# LifeBoardV1_2.net
KiCad netlist of a schematic drawn in EAGLE
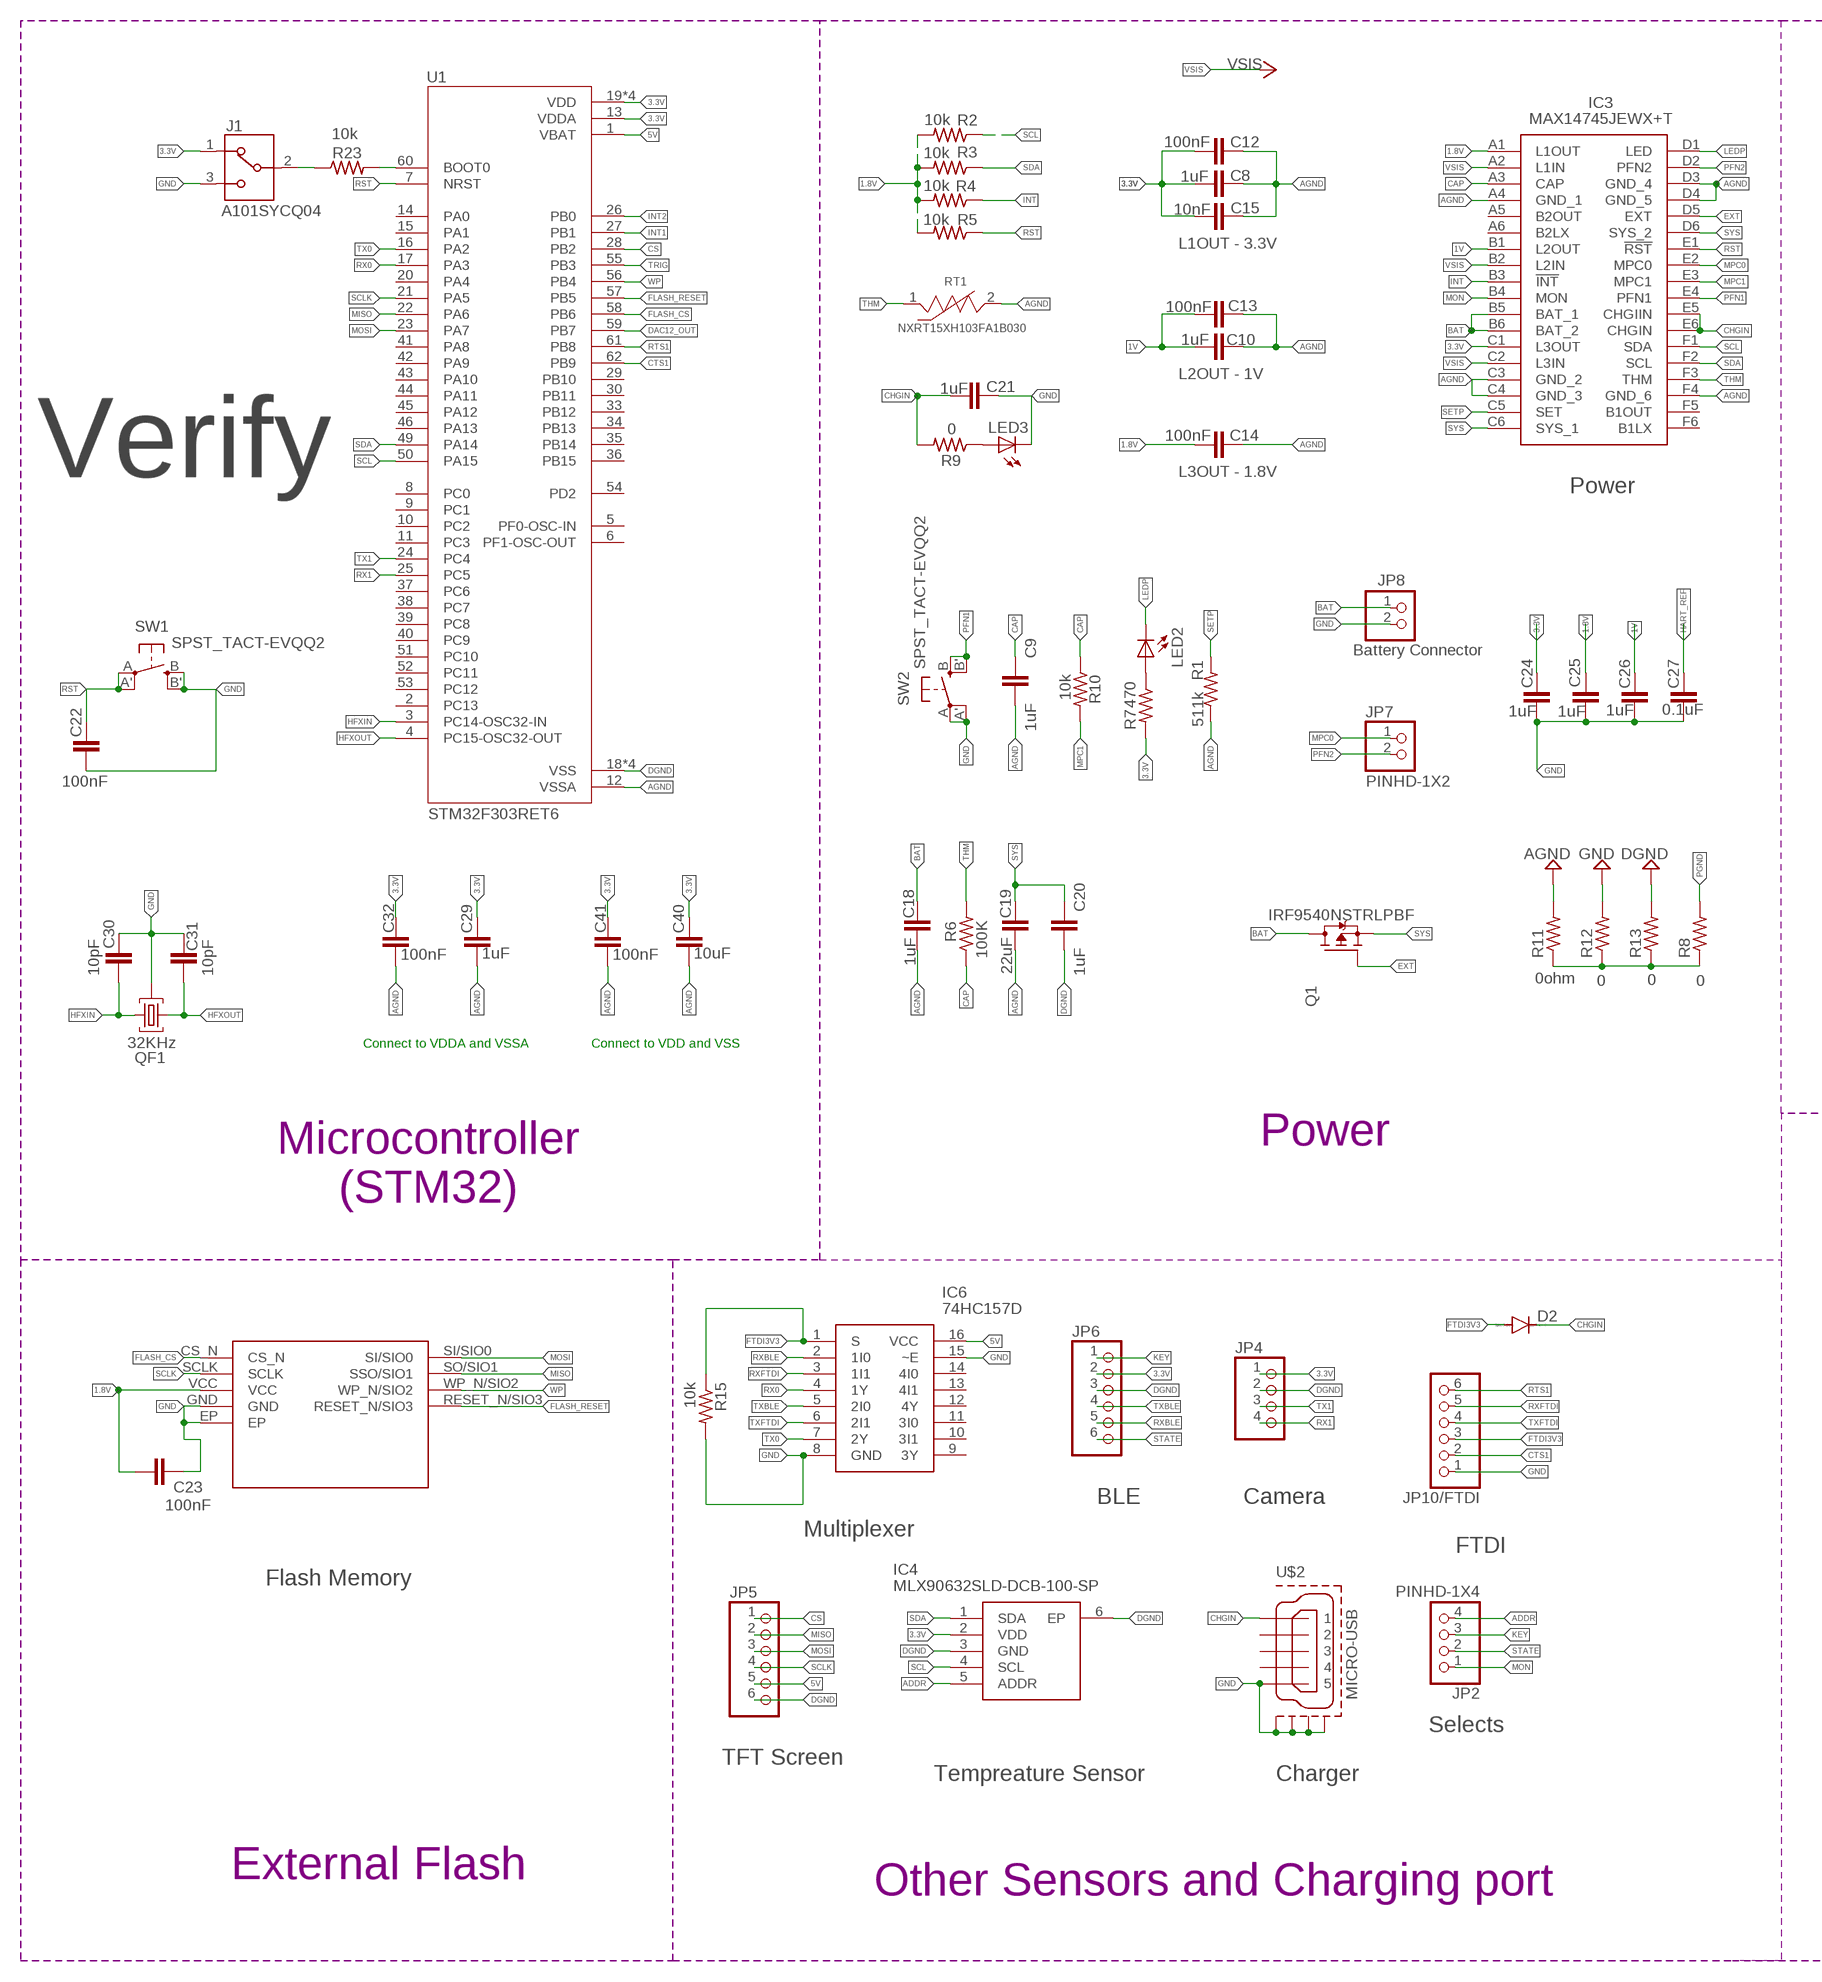
[diagram p0: schematic, sheet 1, part 1 of 2]
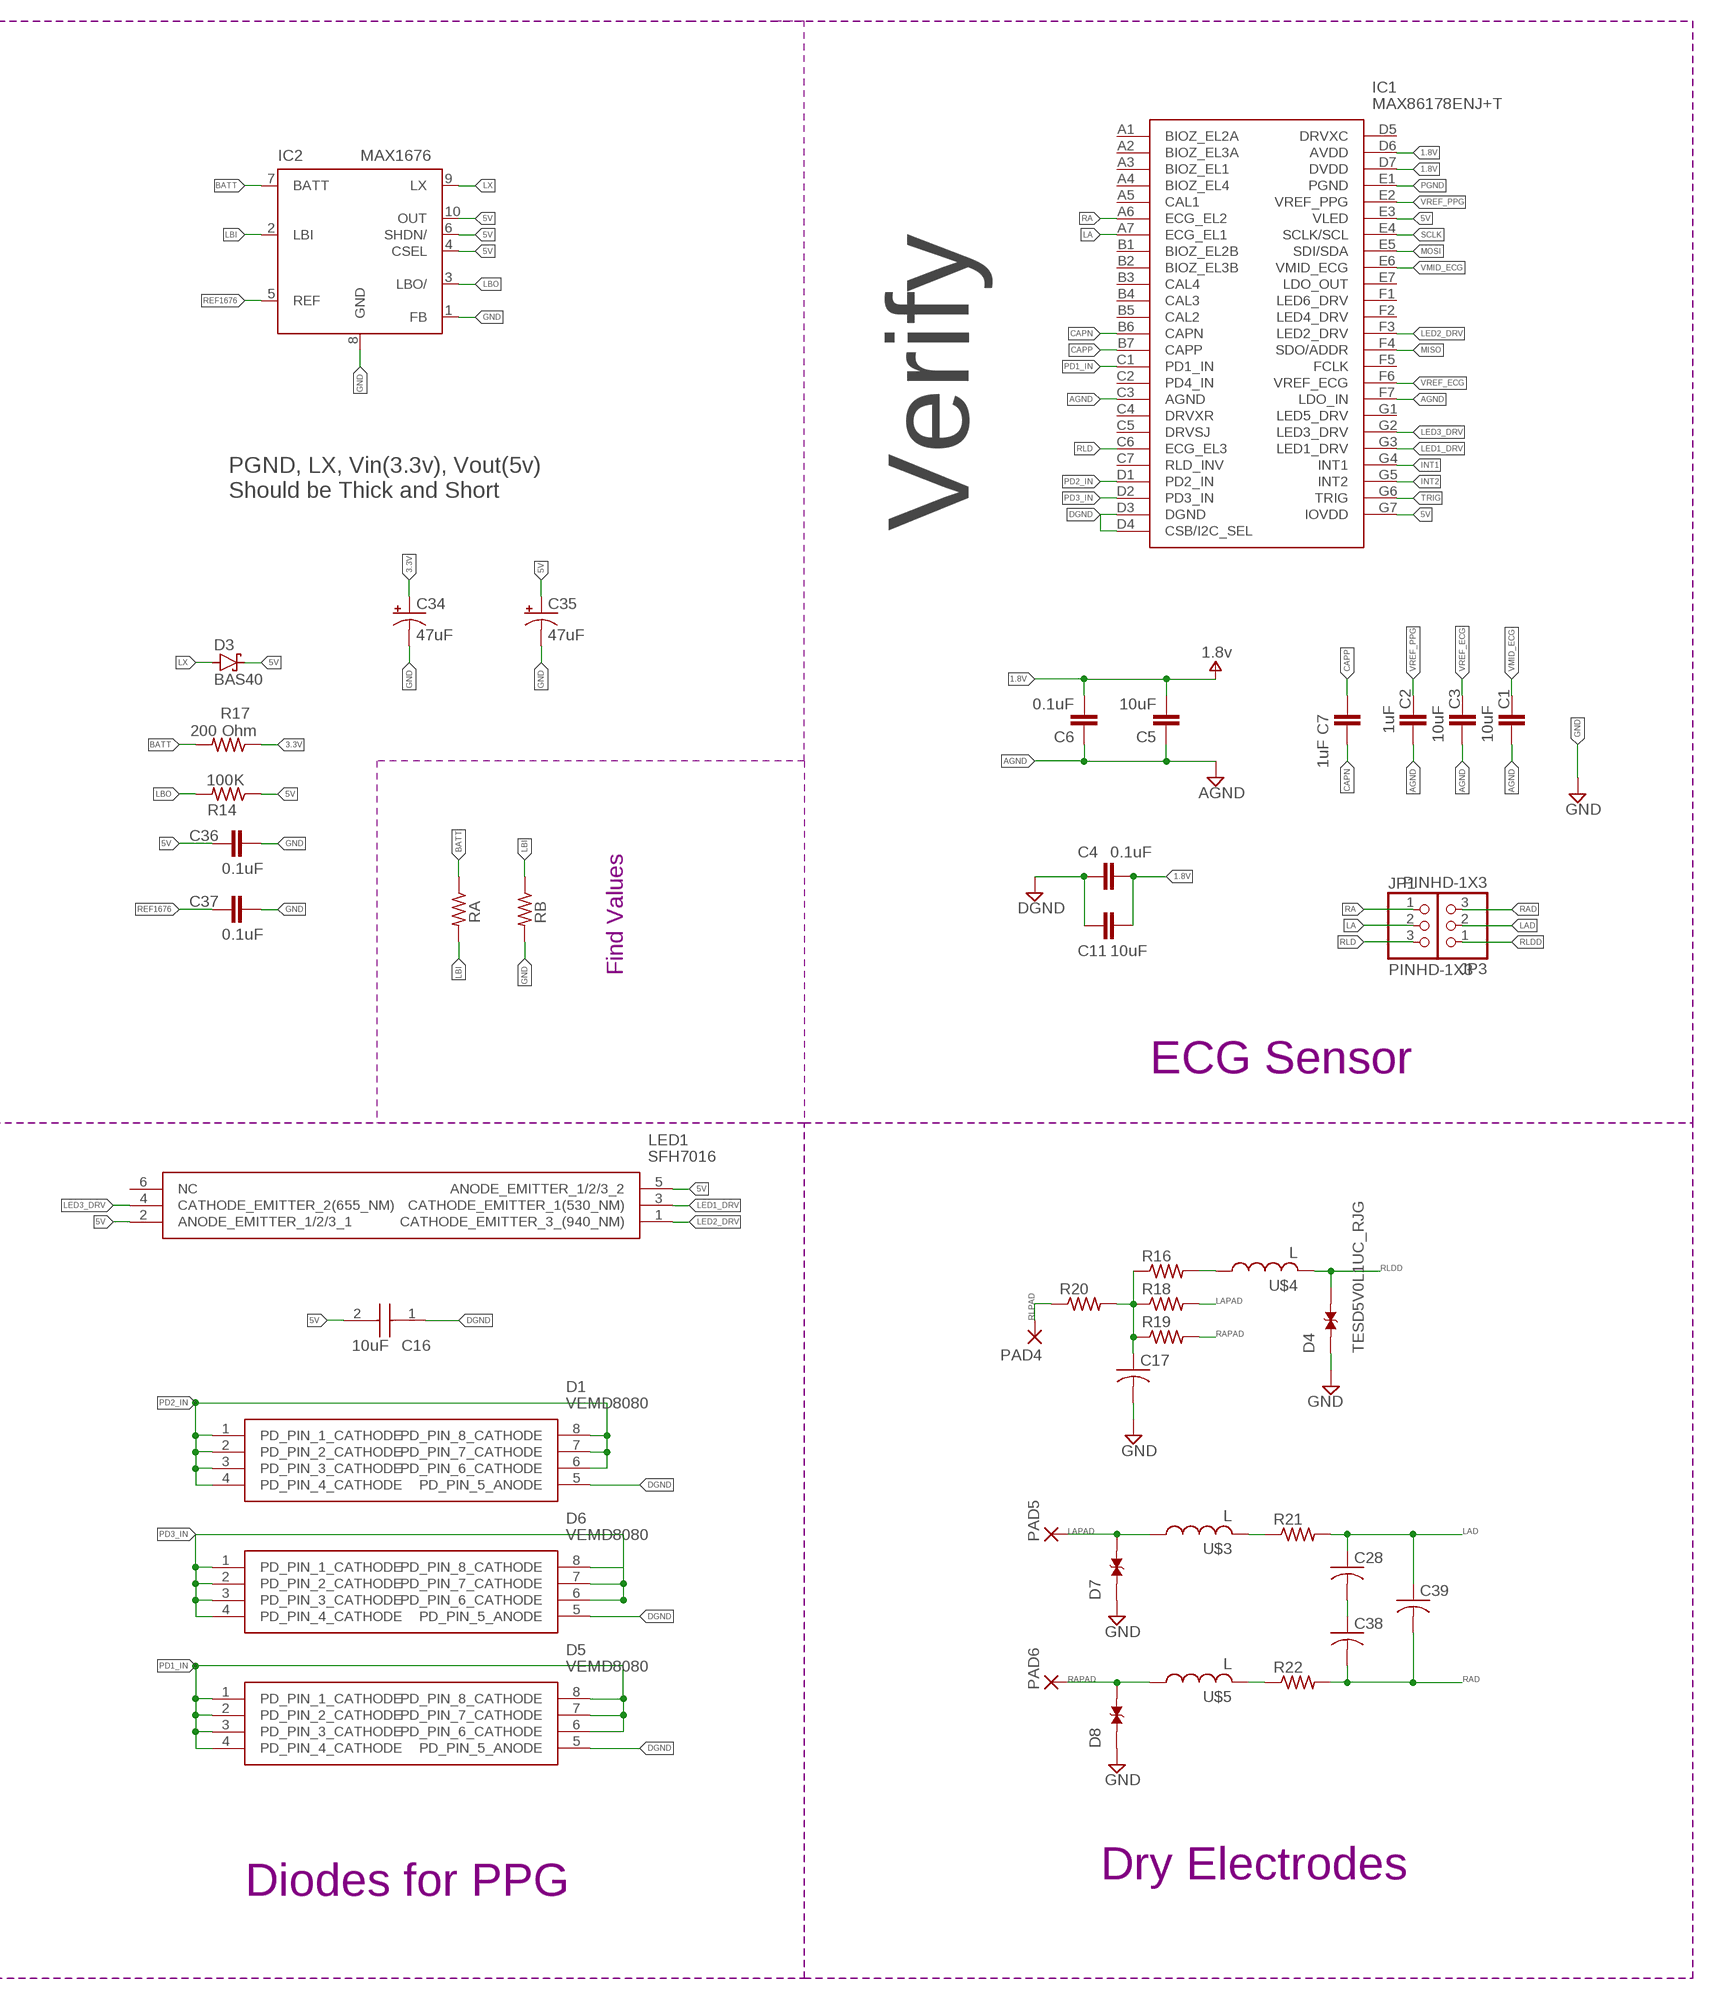
[diagram p1: schematic, sheet 1, part 2 of 2]

(export (version "E")
  (design (tool "Eeschema 10.0.6"))
  (components
    (comp (ref "C1")
      (value "10uF")
      (footprint "eagle-import:C0805")
      (libsource (lib "eagle-import") (part "C-EUC0805"))
    )
    (comp (ref "C2")
      (value "1uF")
      (footprint "eagle-import:C0805")
      (libsource (lib "eagle-import") (part "C-EUC0805"))
    )
    (comp (ref "C3")
      (value "10uF")
      (footprint "eagle-import:C0805")
      (libsource (lib "eagle-import") (part "C-EUC0805"))
    )
    (comp (ref "C4")
      (value "0.1uF")
      (footprint "eagle-import:C0805")
      (libsource (lib "eagle-import") (part "C-EUC0805"))
    )
    (comp (ref "C5")
      (value "10uF")
      (footprint "eagle-import:C0805")
      (libsource (lib "eagle-import") (part "C-EUC0805"))
    )
    (comp (ref "C6")
      (value "0.1uF")
      (footprint "eagle-import:C0805")
      (libsource (lib "eagle-import") (part "C-EUC0805"))
    )
    (comp (ref "C7")
      (value "1uF")
      (footprint "eagle-import:C0805")
      (libsource (lib "eagle-import") (part "C-EUC0805"))
    )
    (comp (ref "C8")
      (value "1uF")
      (footprint "eagle-import:C0805")
      (libsource (lib "eagle-import") (part "C-EUC0805"))
    )
    (comp (ref "C9")
      (value "1uF")
      (footprint "eagle-import:C0805")
      (libsource (lib "eagle-import") (part "C-EUC0805"))
    )
    (comp (ref "C10")
      (value "1uF")
      (footprint "eagle-import:C0805")
      (libsource (lib "eagle-import") (part "C-EUC0805"))
    )
    (comp (ref "C11")
      (value "10uF")
      (footprint "eagle-import:C0805")
      (libsource (lib "eagle-import") (part "C-EUC0805"))
    )
    (comp (ref "C12")
      (value "100nF")
      (footprint "eagle-import:C0805")
      (libsource (lib "eagle-import") (part "C-EUC0805"))
    )
    (comp (ref "C13")
      (value "100nF")
      (footprint "eagle-import:C0805")
      (libsource (lib "eagle-import") (part "C-EUC0805"))
    )
    (comp (ref "C14")
      (value "100nF")
      (footprint "eagle-import:C0805")
      (libsource (lib "eagle-import") (part "C-EUC0805"))
    )
    (comp (ref "C15")
      (value "10nF")
      (footprint "eagle-import:C0805")
      (libsource (lib "eagle-import") (part "C-EUC0805"))
    )
    (comp (ref "C16")
      (value "10uF")
      (footprint "eagle-import:CAPC1608X90N")
      (fields
        (field (name "ARROW_PART_NUMBER") "GRM188R61E106MA73L")
        (field (name "MOUSER_PART_NUMBER") "81-GRM188R61E106MA3L")
      )
      (libsource (lib "eagle-import") (part "GRM188R61E106MA73L"))
    )
    (comp (ref "C17")
      (value "C-US025-024X044")
      (footprint "eagle-import:C025-024X044")
      (libsource (lib "eagle-import") (part "C-US025-024X044"))
    )
    (comp (ref "C18")
      (value "1uF")
      (footprint "eagle-import:C0805")
      (libsource (lib "eagle-import") (part "C-EUC0805"))
    )
    (comp (ref "C19")
      (value "22uF")
      (footprint "eagle-import:C0805")
      (libsource (lib "eagle-import") (part "C-EUC0805"))
    )
    (comp (ref "C20")
      (value "1uF")
      (footprint "eagle-import:C0805")
      (libsource (lib "eagle-import") (part "C-EUC0805"))
    )
    (comp (ref "C21")
      (value "1uF")
      (footprint "eagle-import:C0805")
      (libsource (lib "eagle-import") (part "C-EUC0805"))
    )
    (comp (ref "C22")
      (value "100nF")
      (footprint "eagle-import:C0805")
      (libsource (lib "eagle-import") (part "C-EUC0805"))
    )
    (comp (ref "C23")
      (value "100nF")
      (footprint "eagle-import:C0805")
      (libsource (lib "eagle-import") (part "C-EUC0805"))
    )
    (comp (ref "C24")
      (value "1uF")
      (footprint "eagle-import:C0805")
      (libsource (lib "eagle-import") (part "C-EUC0805"))
    )
    (comp (ref "C25")
      (value "1uF")
      (footprint "eagle-import:C0805")
      (libsource (lib "eagle-import") (part "C-EUC0805"))
    )
    (comp (ref "C26")
      (value "1uF")
      (footprint "eagle-import:C0805")
      (libsource (lib "eagle-import") (part "C-EUC0805"))
    )
    (comp (ref "C27")
      (value "0.1uF")
      (footprint "eagle-import:C0805")
      (libsource (lib "eagle-import") (part "C-EUC0805"))
    )
    (comp (ref "C28")
      (value "C-US025-024X044")
      (footprint "eagle-import:C025-024X044")
      (libsource (lib "eagle-import") (part "C-US025-024X044"))
    )
    (comp (ref "C29")
      (value "1uF")
      (footprint "eagle-import:C0805")
      (libsource (lib "eagle-import") (part "C-EUC0805"))
    )
    (comp (ref "C30")
      (value "10pF")
      (footprint "eagle-import:C0805")
      (libsource (lib "eagle-import") (part "C-EUC0805"))
    )
    (comp (ref "C31")
      (value "10pF")
      (footprint "eagle-import:C0805")
      (libsource (lib "eagle-import") (part "C-EUC0805"))
    )
    (comp (ref "C32")
      (value "100nF")
      (footprint "eagle-import:C0805")
      (libsource (lib "eagle-import") (part "C-EUC0805"))
    )
    (comp (ref "C34")
      (value "47uF")
      (footprint "eagle-import:153CLV-0405")
      (libsource (lib "eagle-import") (part "CPOL-US153CLV-0405"))
    )
    (comp (ref "C35")
      (value "47uF")
      (footprint "eagle-import:153CLV-0405")
      (libsource (lib "eagle-import") (part "CPOL-US153CLV-0405"))
    )
    (comp (ref "C36")
      (value "0.1uF")
      (footprint "eagle-import:C0805")
      (libsource (lib "eagle-import") (part "C-EUC0805"))
    )
    (comp (ref "C37")
      (value "0.1uF")
      (footprint "eagle-import:C0805")
      (libsource (lib "eagle-import") (part "C-EUC0805"))
    )
    (comp (ref "C38")
      (value "C-US025-024X044")
      (footprint "eagle-import:C025-024X044")
      (libsource (lib "eagle-import") (part "C-US025-024X044"))
    )
    (comp (ref "C39")
      (value "C-US025-024X044")
      (footprint "eagle-import:C025-024X044")
      (libsource (lib "eagle-import") (part "C-US025-024X044"))
    )
    (comp (ref "C40")
      (value "10uF")
      (footprint "eagle-import:C0805")
      (libsource (lib "eagle-import") (part "C-EUC0805"))
    )
    (comp (ref "C41")
      (value "100nF")
      (footprint "eagle-import:C0805")
      (libsource (lib "eagle-import") (part "C-EUC0805"))
    )
    (comp (ref "D1")
      (value "VEMD8080")
      (footprint "eagle-import:VEMD8080")
      (fields (field (name "MOUSER_PART_NUMBER") "78-VEMD8080"))
      (libsource (lib "eagle-import") (part "VEMD8080"))
    )
    (comp (ref "D2")
      (value "CGRM4001-G")
      (footprint "eagle-import:SOD-123_MINI-SMA")
      (libsource (lib "eagle-import") (part "CGRM400-G1"))
    )
    (comp (ref "D3")
      (value "BAS40")
      (footprint "eagle-import:SOT23")
      (libsource (lib "eagle-import") (part "BAS40"))
    )
    (comp (ref "D4")
      (value "TESD5V0L1UC_RJG")
      (footprint "eagle-import:DIO_TESD5V0L1UC_RJG")
      (fields (field (name "MF") "Taiwan Semiconductor Corporation") (field (name "MP") "TESD5V0L1UC RJG"))
      (libsource (lib "eagle-import") (part "TESD5V0L1UC_RJG"))
    )
    (comp (ref "D5")
      (value "VEMD8080")
      (footprint "eagle-import:VEMD8080")
      (fields (field (name "MOUSER_PART_NUMBER") "78-VEMD8080"))
      (libsource (lib "eagle-import") (part "VEMD8080"))
    )
    (comp (ref "D6")
      (value "VEMD8080")
      (footprint "eagle-import:VEMD8080")
      (fields (field (name "MOUSER_PART_NUMBER") "78-VEMD8080"))
      (libsource (lib "eagle-import") (part "VEMD8080"))
    )
    (comp (ref "D7")
      (value "TESD5V0L1UC_RJG")
      (footprint "eagle-import:DIO_TESD5V0L1UC_RJG")
      (fields (field (name "MF") "Taiwan Semiconductor Corporation") (field (name "MP") "TESD5V0L1UC RJG"))
      (libsource (lib "eagle-import") (part "TESD5V0L1UC_RJG"))
    )
    (comp (ref "D8")
      (value "TESD5V0L1UC_RJG")
      (footprint "eagle-import:DIO_TESD5V0L1UC_RJG")
      (fields (field (name "MF") "Taiwan Semiconductor Corporation") (field (name "MP") "TESD5V0L1UC RJG"))
      (libsource (lib "eagle-import") (part "TESD5V0L1UC_RJG"))
    )
    (comp (ref "IC1")
      (value "MAX86178ENJ+T")
      (footprint "eagle-import:BGA49C35P7X7_277X257X50")
      (fields (field (name "MOUSER_PART_NUMBER") "700-MAX86178ENJ+T"))
      (libsource (lib "eagle-import") (part "MAX86178ENJ+T"))
    )
    (comp (ref "IC2")
      (value "MAX1676")
      (footprint "eagle-import:UMAX10")
      (fields (field (name "MF") "Maxim Integrated"))
      (libsource (lib "eagle-import") (part "MAX1676"))
    )
    (comp (ref "IC3")
      (value "MAX14745JEWX+T")
      (footprint "eagle-import:BGA36C40P6X6_269X244X69")
      (fields (field (name "MOUSER_PART_NUMBER") "700-MAX14745JEWX+T"))
      (libsource (lib "eagle-import") (part "MAX14745JEWX+T"))
    )
    (comp (ref "IC4")
      (value "MLX90632SLD-DCB-100-SP")
      (footprint "eagle-import:MLX90632SLDDCB100SP")
      (fields (field (name "MOUSER_PART_NUMBER") "482-90632SLDDCB100SP"))
      (libsource (lib "eagle-import") (part "MLX90632SLD-DCB-100-SP"))
    )
    (comp (ref "IC6")
      (value "74HC157D")
      (footprint "eagle-import:SOIC127P600X175-16N")
      (fields (field (name "MOUSER_PART_NUMBER") "771-74HC157D"))
      (libsource (lib "eagle-import") (part "74HC157D"))
    )
    (comp (ref "J1")
      (value "A101SYCQ04")
      (footprint "eagle-import:TE_A101SYCQ04")
      (fields (field (name "COMMENT") "4-1825136-5") (field (name "MF") "TE Connectivity"))
      (libsource (lib "eagle-import") (part "A101SYCQ04"))
    )
    (comp (ref "JP1")
      (value "PINHD-1X3")
      (footprint "eagle-import:1X03")
      (libsource (lib "eagle-import") (part "PINHD-1X3"))
    )
    (comp (ref "JP2")
      (value "PINHD-1X4")
      (footprint "eagle-import:1X04")
      (libsource (lib "eagle-import") (part "PINHD-1X4"))
    )
    (comp (ref "JP3")
      (value "PINHD-1X3")
      (footprint "eagle-import:1X03")
      (libsource (lib "eagle-import") (part "PINHD-1X3"))
    )
    (comp (ref "JP4")
      (value "PINHD-1X4")
      (footprint "eagle-import:1X04")
      (libsource (lib "eagle-import") (part "pinhead_325_PINHD-1X4"))
    )
    (comp (ref "JP5")
      (value "PINHD-1X6")
      (footprint "eagle-import:1X06")
      (libsource (lib "eagle-import") (part "PINHD-1X6"))
    )
    (comp (ref "JP6")
      (value "PINHD-1X6")
      (footprint "eagle-import:1X06")
      (libsource (lib "eagle-import") (part "PINHD-1X6"))
    )
    (comp (ref "JP7")
      (value "PINHD-1X2")
      (footprint "eagle-import:1X02")
      (libsource (lib "eagle-import") (part "PINHD-1X2"))
    )
    (comp (ref "JP8")
      (value "Battery Connector")
      (footprint "eagle-import:1X02")
      (libsource (lib "eagle-import") (part "PINHD-1X2"))
    )
    (comp (ref "JP10/FTDI")
      (value "PINHD-1X6")
      (footprint "eagle-import:1X06")
      (libsource (lib "eagle-import") (part "PINHD-1X6"))
    )
    (comp (ref "LED1")
      (value "SFH7016")
      (footprint "eagle-import:SFH7016")
      (libsource (lib "eagle-import") (part "SFH7016"))
    )
    (comp (ref "LED2")
      (value "LEDCHIPLED_1206")
      (footprint "eagle-import:CHIPLED_1206")
      (libsource (lib "eagle-import") (part "LEDCHIPLED_1206"))
    )
    (comp (ref "LED3")
      (value "LEDCHIPLED_1206")
      (footprint "eagle-import:CHIPLED_1206")
      (libsource (lib "eagle-import") (part "LEDCHIPLED_1206"))
    )
    (comp (ref "PAD4")
      (value "SMD5")
      (footprint "eagle-import:SMD2,54-5,08")
      (libsource (lib "eagle-import") (part "SMD5"))
    )
    (comp (ref "PAD5")
      (value "SMD5")
      (footprint "eagle-import:SMD2,54-5,08")
      (libsource (lib "eagle-import") (part "SMD5"))
    )
    (comp (ref "PAD6")
      (value "SMD5")
      (footprint "eagle-import:SMD2,54-5,08")
      (libsource (lib "eagle-import") (part "SMD5"))
    )
    (comp (ref "Q1")
      (value "IRF9540NSTRLPBF")
      (footprint "eagle-import:DPAK254P1524X483-4_3N")
      (fields (field (name "MF") "Infineon"))
      (libsource (lib "eagle-import") (part "IRF9540NSTRLPBF"))
    )
    (comp (ref "QF1")
      (value "32KHz")
      (footprint "eagle-import:HC49U")
      (libsource (lib "eagle-import") (part "8M10AHC49T"))
    )
    (comp (ref "R1")
      (value "511k")
      (footprint "eagle-import:M1206")
      (libsource (lib "eagle-import") (part "R-US_M1206"))
    )
    (comp (ref "R2")
      (value "10k")
      (footprint "eagle-import:M1206")
      (libsource (lib "eagle-import") (part "R-US_M1206"))
    )
    (comp (ref "R3")
      (value "10k")
      (footprint "eagle-import:M1206")
      (libsource (lib "eagle-import") (part "R-US_M1206"))
    )
    (comp (ref "R4")
      (value "10k")
      (footprint "eagle-import:M1206")
      (libsource (lib "eagle-import") (part "R-US_M1206"))
    )
    (comp (ref "R5")
      (value "10k")
      (footprint "eagle-import:M1206")
      (libsource (lib "eagle-import") (part "R-US_M1206"))
    )
    (comp (ref "R6")
      (value "100K")
      (footprint "eagle-import:M1206")
      (libsource (lib "eagle-import") (part "R-US_M1206"))
    )
    (comp (ref "R7")
      (value "470")
      (footprint "eagle-import:M1206")
      (libsource (lib "eagle-import") (part "R-US_M1206"))
    )
    (comp (ref "R8")
      (value "0")
      (footprint "eagle-import:R1206")
      (libsource (lib "eagle-import") (part "R-US_R1206"))
    )
    (comp (ref "R9")
      (value "0")
      (footprint "eagle-import:R1206")
      (libsource (lib "eagle-import") (part "R-US_R1206"))
    )
    (comp (ref "R10")
      (value "10k")
      (footprint "eagle-import:M1206")
      (libsource (lib "eagle-import") (part "R-US_M1206"))
    )
    (comp (ref "R11")
      (value "0ohm")
      (footprint "eagle-import:R1206")
      (libsource (lib "eagle-import") (part "R-US_R1206"))
    )
    (comp (ref "R12")
      (value "0")
      (footprint "eagle-import:R1206")
      (libsource (lib "eagle-import") (part "R-US_R1206"))
    )
    (comp (ref "R13")
      (value "0")
      (footprint "eagle-import:R1206")
      (libsource (lib "eagle-import") (part "R-US_R1206"))
    )
    (comp (ref "R14")
      (value "100K")
      (footprint "eagle-import:R1206")
      (libsource (lib "eagle-import") (part "R-US_R1206"))
    )
    (comp (ref "R15")
      (value "10k")
      (footprint "eagle-import:M1206")
      (libsource (lib "eagle-import") (part "R-US_M1206"))
    )
    (comp (ref "R16")
      (value "R-US_0207/10")
      (footprint "eagle-import:0207_10")
      (libsource (lib "eagle-import") (part "R-US_0207/10"))
    )
    (comp (ref "R17")
      (value "200 Ohm")
      (footprint "eagle-import:R1206")
      (libsource (lib "eagle-import") (part "R-US_R1206"))
    )
    (comp (ref "R18")
      (value "R-US_0207/10")
      (footprint "eagle-import:0207_10")
      (libsource (lib "eagle-import") (part "R-US_0207/10"))
    )
    (comp (ref "R19")
      (value "R-US_0207/10")
      (footprint "eagle-import:0207_10")
      (libsource (lib "eagle-import") (part "R-US_0207/10"))
    )
    (comp (ref "R20")
      (value "R-US_0207/10")
      (footprint "eagle-import:0207_10")
      (libsource (lib "eagle-import") (part "R-US_0207/10"))
    )
    (comp (ref "R21")
      (value "R-US_0207/10")
      (footprint "eagle-import:0207_10")
      (libsource (lib "eagle-import") (part "R-US_0207/10"))
    )
    (comp (ref "R22")
      (value "R-US_0207/10")
      (footprint "eagle-import:0207_10")
      (libsource (lib "eagle-import") (part "R-US_0207/10"))
    )
    (comp (ref "R23")
      (value "10k")
      (footprint "eagle-import:M1206")
      (libsource (lib "eagle-import") (part "R-US_M1206"))
    )
    (comp (ref "RA")
      (value "R-US_R1206")
      (footprint "eagle-import:R1206")
      (libsource (lib "eagle-import") (part "R-US_R1206"))
    )
    (comp (ref "RB")
      (value "R-US_R1206")
      (footprint "eagle-import:R1206")
      (libsource (lib "eagle-import") (part "R-US_R1206"))
    )
    (comp (ref "RT1")
      (value "NXRT15XH103FA1B030")
      (footprint "eagle-import:THERM_NXRT15XH103FA1B030")
      (fields (field (name "MF") "Murata"))
      (libsource (lib "eagle-import") (part "NXRT15XH103FA1B030"))
    )
    (comp (ref "SW1")
      (value "SPST_TACT-EVQQ2")
      (footprint "eagle-import:EVQ-Q2")
      (libsource (lib "eagle-import") (part "SPST_TACT-EVQQ2"))
    )
    (comp (ref "SW2")
      (value "SPST_TACT-EVQQ2")
      (footprint "eagle-import:EVQ-Q2")
      (libsource (lib "eagle-import") (part "SPST_TACT-EVQQ2"))
    )
    (comp (ref "U$1")
      (value "FLASH")
      (footprint "eagle-import:SON127P600X800X80-9N")
      (libsource (lib "eagle-import") (part "FLASH"))
    )
    (comp (ref "U$2")
      (value "MICRO-USB")
      (footprint "eagle-import:47589-0001")
      (libsource (lib "eagle-import") (part "MICRO-USB-RECEPTACLE47589-0001"))
    )
    (comp (ref "U$3") (value "L") (footprint "eagle-import:6000") (libsource (lib "eagle-import") (part "L")))
    (comp (ref "U$4") (value "L") (footprint "eagle-import:6000") (libsource (lib "eagle-import") (part "L")))
    (comp (ref "U$5") (value "L") (footprint "eagle-import:6000") (libsource (lib "eagle-import") (part "L")))
    (comp (ref "U1")
      (value "STM32F303RET6")
      (footprint "eagle-import:QFP50P1200X1200X160-64N")
      (fields (field (name "MF") "STMicroelectronics"))
      (libsource (lib "eagle-import") (part "STM32F303RET6"))
    )
  )
  (nets
    (net (code "1") (name "/LAPAD") (class "Default")
      (node (ref "D7") (pin "2") (pinfunction "2_2") (pintype "passive"))
      (node (ref "PAD5") (pin "1") (pinfunction "P_1") (pintype "passive"))
      (node (ref "R18") (pin "2") (pinfunction "2_2") (pintype "passive"))
      (node (ref "U$3") (pin "1") (pinfunction "1_1") (pintype "passive"))
    )
    (net (code "2") (name "/RAPAD") (class "Default")
      (node (ref "D8") (pin "2") (pinfunction "2_2") (pintype "passive"))
      (node (ref "PAD6") (pin "1") (pinfunction "P_1") (pintype "passive"))
      (node (ref "R19") (pin "2") (pinfunction "2_2") (pintype "passive"))
      (node (ref "U$5") (pin "1") (pinfunction "1_1") (pintype "passive"))
    )
    (net (code "3") (name "/RLPAD") (class "Default")
      (node (ref "PAD4") (pin "1") (pinfunction "P_1") (pintype "passive"))
      (node (ref "R20") (pin "1") (pinfunction "1_1") (pintype "passive"))
    )
    (net (code "4") (name "1.8V") (class "Default")
      (node (ref "C11") (pin "2") (pinfunction "2_2") (pintype "passive"))
      (node (ref "C14") (pin "2") (pinfunction "2_2") (pintype "passive"))
      (node (ref "C23") (pin "1") (pinfunction "1_1") (pintype "passive"))
      (node (ref "C25") (pin "1") (pinfunction "1_1") (pintype "passive"))
      (node (ref "C4") (pin "2") (pinfunction "2_2") (pintype "passive"))
      (node (ref "C5") (pin "2") (pinfunction "2_2") (pintype "passive"))
      (node (ref "C6") (pin "2") (pinfunction "2_2") (pintype "passive"))
      (node (ref "IC1") (pin "D6") (pinfunction "AVDD_D6") (pintype "bidirectional"))
      (node (ref "IC1") (pin "D7") (pinfunction "DVDD_D7") (pintype "bidirectional"))
      (node (ref "IC3") (pin "A1") (pinfunction "L1OUT_A1") (pintype "bidirectional"))
      (node (ref "R2") (pin "2") (pinfunction "2_2") (pintype "passive"))
      (node (ref "R3") (pin "2") (pinfunction "2_2") (pintype "passive"))
      (node (ref "R4") (pin "2") (pinfunction "2_2") (pintype "passive"))
      (node (ref "R5") (pin "2") (pinfunction "2_2") (pintype "passive"))
      (node (ref "U$1") (pin "VCC") (pinfunction "VCC_VCC") (pintype "bidirectional"))
    )
    (net (code "5") (name "1V") (class "Default")
      (node (ref "C10") (pin "2") (pinfunction "2_2") (pintype "passive"))
      (node (ref "C13") (pin "2") (pinfunction "2_2") (pintype "passive"))
      (node (ref "C26") (pin "1") (pinfunction "1_1") (pintype "passive"))
      (node (ref "IC3") (pin "B1") (pinfunction "L2OUT_B1") (pintype "bidirectional"))
    )
    (net (code "6") (name "3.3V") (class "Default")
      (node (ref "C12") (pin "2") (pinfunction "2_2") (pintype "passive"))
      (node (ref "C15") (pin "2") (pinfunction "2_2") (pintype "passive"))
      (node (ref "C24") (pin "1") (pinfunction "1_1") (pintype "passive"))
      (node (ref "C29") (pin "1") (pinfunction "1_1") (pintype "passive"))
      (node (ref "C32") (pin "1") (pinfunction "1_1") (pintype "passive"))
      (node (ref "C34") (pin "+") (pinfunction "+_+") (pintype "passive"))
      (node (ref "C40") (pin "1") (pinfunction "1_1") (pintype "passive"))
      (node (ref "C41") (pin "1") (pinfunction "1_1") (pintype "passive"))
      (node (ref "C8") (pin "2") (pinfunction "2_2") (pintype "passive"))
      (node (ref "IC3") (pin "C1") (pinfunction "L3OUT_C1") (pintype "bidirectional"))
      (node (ref "IC4") (pin "2") (pinfunction "VDD_2") (pintype "bidirectional"))
      (node (ref "J1") (pin "1") (pinfunction "1_1") (pintype "passive"))
      (node (ref "JP4") (pin "1") (pinfunction "1_1") (pintype "passive"))
      (node (ref "JP6") (pin "2") (pinfunction "2_2") (pintype "passive"))
      (node (ref "R17") (pin "1") (pinfunction "1_1") (pintype "passive"))
      (node (ref "R7") (pin "2") (pinfunction "2_2") (pintype "passive"))
      (node (ref "U1") (pin "13") (pinfunction "VDDA_13") (pintype "power_in"))
      (node (ref "U1") (pin "19") (pinfunction "VDD_19") (pintype "power_in"))
      (node (ref "U1") (pin "32") (pinfunction "VDD_32") (pintype "power_in"))
      (node (ref "U1") (pin "48") (pinfunction "VDD_48") (pintype "power_in"))
      (node (ref "U1") (pin "64") (pinfunction "VDD_64") (pintype "power_in"))
    )
    (net (code "7") (name "5V") (class "Default")
      (node (ref "C16") (pin "2") (pinfunction "2_2") (pintype "bidirectional"))
      (node (ref "C35") (pin "+") (pinfunction "+_+") (pintype "passive"))
      (node (ref "C36") (pin "1") (pinfunction "1_1") (pintype "passive"))
      (node (ref "D3") (pin "3") (pinfunction "C_3") (pintype "passive"))
      (node (ref "IC1") (pin "E3") (pinfunction "VLED_E3") (pintype "bidirectional"))
      (node (ref "IC1") (pin "G7") (pinfunction "IOVDD_G7") (pintype "bidirectional"))
      (node (ref "IC2") (pin "10") (pinfunction "OUT_10") (pintype "output"))
      (node (ref "IC2") (pin "4") (pinfunction "CSEL_4") (pintype "input"))
      (node (ref "IC2") (pin "6") (pinfunction "SHDN/_6") (pintype "input"))
      (node (ref "IC6") (pin "16") (pinfunction "VCC_16") (pintype "bidirectional"))
      (node (ref "JP5") (pin "5") (pinfunction "5_5") (pintype "passive"))
      (node (ref "LED1") (pin "2") (pinfunction "ANODE_EMITTER_1/2/3_1_2") (pintype "bidirectional"))
      (node (ref "LED1") (pin "5") (pinfunction "ANODE_EMITTER_1/2/3_2_5") (pintype "bidirectional"))
      (node (ref "R14") (pin "1") (pinfunction "1_1") (pintype "passive"))
      (node (ref "U1") (pin "1") (pinfunction "VBAT_1") (pintype "power_in"))
    )
    (net (code "8") (name "ADDR") (class "Default")
      (node (ref "IC4") (pin "5") (pinfunction "ADDR_5") (pintype "bidirectional"))
      (node (ref "JP2") (pin "4") (pinfunction "4_4") (pintype "passive"))
    )
    (net (code "9") (name "AGND") (class "Default")
      (node (ref "C1") (pin "1") (pinfunction "1_1") (pintype "passive"))
      (node (ref "C10") (pin "1") (pinfunction "1_1") (pintype "passive"))
      (node (ref "C12") (pin "1") (pinfunction "1_1") (pintype "passive"))
      (node (ref "C13") (pin "1") (pinfunction "1_1") (pintype "passive"))
      (node (ref "C14") (pin "1") (pinfunction "1_1") (pintype "passive"))
      (node (ref "C15") (pin "1") (pinfunction "1_1") (pintype "passive"))
      (node (ref "C18") (pin "2") (pinfunction "2_2") (pintype "passive"))
      (node (ref "C19") (pin "2") (pinfunction "2_2") (pintype "passive"))
      (node (ref "C2") (pin "1") (pinfunction "1_1") (pintype "passive"))
      (node (ref "C29") (pin "2") (pinfunction "2_2") (pintype "passive"))
      (node (ref "C3") (pin "1") (pinfunction "1_1") (pintype "passive"))
      (node (ref "C32") (pin "2") (pinfunction "2_2") (pintype "passive"))
      (node (ref "C40") (pin "2") (pinfunction "2_2") (pintype "passive"))
      (node (ref "C41") (pin "2") (pinfunction "2_2") (pintype "passive"))
      (node (ref "C5") (pin "1") (pinfunction "1_1") (pintype "passive"))
      (node (ref "C6") (pin "1") (pinfunction "1_1") (pintype "passive"))
      (node (ref "C8") (pin "1") (pinfunction "1_1") (pintype "passive"))
      (node (ref "C9") (pin "2") (pinfunction "2_2") (pintype "passive"))
      (node (ref "IC1") (pin "C3") (pinfunction "AGND_C3") (pintype "bidirectional"))
      (node (ref "IC1") (pin "F7") (pinfunction "LDO_IN_F7") (pintype "bidirectional"))
      (node (ref "IC3") (pin "A4") (pinfunction "GND_1_A4") (pintype "bidirectional"))
      (node (ref "IC3") (pin "C3") (pinfunction "GND_2_C3") (pintype "bidirectional"))
      (node (ref "IC3") (pin "C4") (pinfunction "GND_3_C4") (pintype "bidirectional"))
      (node (ref "IC3") (pin "D3") (pinfunction "GND_4_D3") (pintype "bidirectional"))
      (node (ref "IC3") (pin "D4") (pinfunction "GND_5_D4") (pintype "bidirectional"))
      (node (ref "IC3") (pin "F4") (pinfunction "GND_6_F4") (pintype "bidirectional"))
      (node (ref "R1") (pin "1") (pinfunction "1_1") (pintype "passive"))
      (node (ref "R11") (pin "2") (pinfunction "2_2") (pintype "passive"))
      (node (ref "RT1") (pin "2") (pinfunction "2_2") (pintype "passive"))
      (node (ref "U1") (pin "12") (pinfunction "VSSA_12") (pintype "power_in"))
    )
    (net (code "10") (name "BAT") (class "Default")
      (node (ref "C18") (pin "1") (pinfunction "1_1") (pintype "passive"))
      (node (ref "IC3") (pin "B5") (pinfunction "BAT_1_B5") (pintype "bidirectional"))
      (node (ref "IC3") (pin "B6") (pinfunction "BAT_2_B6") (pintype "bidirectional"))
      (node (ref "JP8") (pin "1") (pinfunction "1_1") (pintype "passive"))
      (node (ref "Q1") (pin "4") (pinfunction "D_4") (pintype "passive"))
    )
    (net (code "11") (name "BATT") (class "Default")
      (node (ref "IC2") (pin "7") (pinfunction "BATT_7") (pintype "input"))
      (node (ref "R17") (pin "2") (pinfunction "2_2") (pintype "passive"))
      (node (ref "RA") (pin "1") (pinfunction "1_1") (pintype "passive"))
    )
    (net (code "12") (name "CAP") (class "Default")
      (node (ref "C9") (pin "1") (pinfunction "1_1") (pintype "passive"))
      (node (ref "IC3") (pin "A3") (pinfunction "CAP_A3") (pintype "bidirectional"))
      (node (ref "R10") (pin "1") (pinfunction "1_1") (pintype "passive"))
      (node (ref "R6") (pin "1") (pinfunction "1_1") (pintype "passive"))
    )
    (net (code "13") (name "CAPN") (class "Default")
      (node (ref "C7") (pin "2") (pinfunction "2_2") (pintype "passive"))
      (node (ref "IC1") (pin "B6") (pinfunction "CAPN_B6") (pintype "bidirectional"))
    )
    (net (code "14") (name "CAPP") (class "Default")
      (node (ref "C7") (pin "1") (pinfunction "1_1") (pintype "passive"))
      (node (ref "IC1") (pin "B7") (pinfunction "CAPP_B7") (pintype "bidirectional"))
    )
    (net (code "15") (name "CHGIN") (class "Default")
      (node (ref "C21") (pin "2") (pinfunction "2_2") (pintype "passive"))
      (node (ref "D2") (pin "C") (pinfunction "C_C") (pintype "passive"))
      (node (ref "IC3") (pin "E5") (pinfunction "CHGIIN_E5") (pintype "bidirectional"))
      (node (ref "IC3") (pin "E6") (pinfunction "CHGIN_E6") (pintype "bidirectional"))
      (node (ref "R9") (pin "2") (pinfunction "2_2") (pintype "passive"))
      (node (ref "U$2") (pin "1") (pinfunction "1_1") (pintype "input"))
    )
    (net (code "16") (name "CS") (class "Default")
      (node (ref "JP5") (pin "1") (pinfunction "1_1") (pintype "passive"))
      (node (ref "U1") (pin "28") (pinfunction "PB2_28") (pintype "bidirectional"))
    )
    (net (code "17") (name "CTS1") (class "Default")
      (node (ref "JP10/FTDI") (pin "2") (pinfunction "2_2") (pintype "passive"))
      (node (ref "U1") (pin "62") (pinfunction "PB9_62") (pintype "bidirectional"))
    )
    (net (code "18") (name "DAC12_OUT") (class "Default")
      (node (ref "U1") (pin "59") (pinfunction "PB7_59") (pintype "bidirectional"))
    )
    (net (code "19") (name "DGND") (class "Default")
      (node (ref "C11") (pin "1") (pinfunction "1_1") (pintype "passive"))
      (node (ref "C16") (pin "1") (pinfunction "1_1") (pintype "bidirectional"))
      (node (ref "C20") (pin "2") (pinfunction "2_2") (pintype "passive"))
      (node (ref "C4") (pin "1") (pinfunction "1_1") (pintype "passive"))
      (node (ref "D1") (pin "5") (pinfunction "PD_PIN_5_ANODE_5") (pintype "bidirectional"))
      (node (ref "D5") (pin "5") (pinfunction "PD_PIN_5_ANODE_5") (pintype "bidirectional"))
      (node (ref "D6") (pin "5") (pinfunction "PD_PIN_5_ANODE_5") (pintype "bidirectional"))
      (node (ref "IC1") (pin "D3") (pinfunction "DGND_D3") (pintype "bidirectional"))
      (node (ref "IC1") (pin "D4") (pinfunction "CSB/I2C_SEL_D4") (pintype "bidirectional"))
      (node (ref "IC4") (pin "3") (pinfunction "GND_3") (pintype "bidirectional"))
      (node (ref "IC4") (pin "6") (pinfunction "EP_6") (pintype "bidirectional"))
      (node (ref "JP4") (pin "2") (pinfunction "2_2") (pintype "passive"))
      (node (ref "JP5") (pin "6") (pinfunction "6_6") (pintype "passive"))
      (node (ref "JP6") (pin "3") (pinfunction "3_3") (pintype "passive"))
      (node (ref "R13") (pin "2") (pinfunction "2_2") (pintype "passive"))
      (node (ref "U1") (pin "18") (pinfunction "VSS_18") (pintype "power_in"))
      (node (ref "U1") (pin "31") (pinfunction "VSS_31") (pintype "power_in"))
      (node (ref "U1") (pin "47") (pinfunction "VSS_47") (pintype "power_in"))
      (node (ref "U1") (pin "63") (pinfunction "VSS_63") (pintype "power_in"))
    )
    (net (code "20") (name "EXT") (class "Default")
      (node (ref "IC3") (pin "D5") (pinfunction "EXT_D5") (pintype "bidirectional"))
      (node (ref "Q1") (pin "1") (pinfunction "G_1") (pintype "passive"))
    )
    (net (code "21") (name "FLASH_CS") (class "Default")
      (node (ref "U$1") (pin "CS_N") (pinfunction "CS_N_CS_N") (pintype "bidirectional"))
      (node (ref "U1") (pin "58") (pinfunction "PB6_58") (pintype "bidirectional"))
    )
    (net (code "22") (name "FLASH_RESET") (class "Default")
      (node (ref "U$1") (pin "RESET_N/SIO3") (pinfunction "RESET_N/SIO3_RESET_N/SIO3") (pintype "bidirectional"))
      (node (ref "U1") (pin "57") (pinfunction "PB5_57") (pintype "bidirectional"))
    )
    (net (code "23") (name "FTDI3V3") (class "Default")
      (node (ref "D2") (pin "A") (pinfunction "A_A") (pintype "passive"))
      (node (ref "IC6") (pin "1") (pinfunction "S_1") (pintype "bidirectional"))
      (node (ref "JP10/FTDI") (pin "3") (pinfunction "3_3") (pintype "passive"))
      (node (ref "R15") (pin "1") (pinfunction "1_1") (pintype "passive"))
    )
    (net (code "24") (name "GND") (class "Default")
      (node (ref "C17") (pin "2") (pinfunction "2_2") (pintype "passive"))
      (node (ref "C21") (pin "1") (pinfunction "1_1") (pintype "passive"))
      (node (ref "C22") (pin "2") (pinfunction "2_2") (pintype "passive"))
      (node (ref "C23") (pin "2") (pinfunction "2_2") (pintype "passive"))
      (node (ref "C24") (pin "2") (pinfunction "2_2") (pintype "passive"))
      (node (ref "C25") (pin "2") (pinfunction "2_2") (pintype "passive"))
      (node (ref "C26") (pin "2") (pinfunction "2_2") (pintype "passive"))
      (node (ref "C27") (pin "2") (pinfunction "2_2") (pintype "passive"))
      (node (ref "C30") (pin "1") (pinfunction "1_1") (pintype "passive"))
      (node (ref "C31") (pin "1") (pinfunction "1_1") (pintype "passive"))
      (node (ref "C34") (pin "-") (pinfunction "-_-") (pintype "passive"))
      (node (ref "C35") (pin "-") (pinfunction "-_-") (pintype "passive"))
      (node (ref "C36") (pin "2") (pinfunction "2_2") (pintype "passive"))
      (node (ref "C37") (pin "2") (pinfunction "2_2") (pintype "passive"))
      (node (ref "D4") (pin "1") (pinfunction "1_1") (pintype "passive"))
      (node (ref "D7") (pin "1") (pinfunction "1_1") (pintype "passive"))
      (node (ref "D8") (pin "1") (pinfunction "1_1") (pintype "passive"))
      (node (ref "IC2") (pin "1") (pinfunction "FB_1") (pintype "input"))
      (node (ref "IC2") (pin "8") (pinfunction "GND_8") (pintype "power_in"))
      (node (ref "IC6") (pin "15") (pinfunction "~{E}_15") (pintype "bidirectional"))
      (node (ref "IC6") (pin "8") (pinfunction "GND_8") (pintype "bidirectional"))
      (node (ref "J1") (pin "3") (pinfunction "3_3") (pintype "passive"))
      (node (ref "JP10/FTDI") (pin "1") (pinfunction "1_1") (pintype "passive"))
      (node (ref "JP8") (pin "2") (pinfunction "2_2") (pintype "passive"))
      (node (ref "LED3") (pin "C") (pinfunction "C_C") (pintype "passive"))
      (node (ref "QF1") (pin "2") (pinfunction "2_2") (pintype "passive"))
      (node (ref "R12") (pin "2") (pinfunction "2_2") (pintype "passive"))
      (node (ref "R15") (pin "2") (pinfunction "2_2") (pintype "passive"))
      (node (ref "RB") (pin "2") (pinfunction "2_2") (pintype "passive"))
      (node (ref "SW1") (pin "B") (pinfunction "S_B") (pintype "passive"))
      (node (ref "SW1") (pin "B'") (pinfunction "S1_B'") (pintype "passive"))
      (node (ref "SW2") (pin "A") (pinfunction "P_A") (pintype "passive"))
      (node (ref "SW2") (pin "A'") (pinfunction "P1_A'") (pintype "passive"))
      (node (ref "U$1") (pin "EP") (pinfunction "EP_EP") (pintype "bidirectional"))
      (node (ref "U$1") (pin "GND") (pinfunction "GND_GND") (pintype "bidirectional"))
      (node (ref "U$2") (pin "5") (pinfunction "5_5") (pintype "input"))
      (node (ref "U$2") (pin "CASING1") (pinfunction "GND1_CASING1") (pintype "bidirectional"))
      (node (ref "U$2") (pin "CASING2") (pinfunction "GND2_CASING2") (pintype "bidirectional"))
      (node (ref "U$2") (pin "CASING3") (pinfunction "GND3_CASING3") (pintype "bidirectional"))
      (node (ref "U$2") (pin "CASING4") (pinfunction "GND4_CASING4") (pintype "bidirectional"))
    )
    (net (code "25") (name "HART_REF") (class "Default")
      (node (ref "C27") (pin "1") (pinfunction "1_1") (pintype "passive"))
    )
    (net (code "26") (name "HFXIN") (class "Default")
      (node (ref "C30") (pin "2") (pinfunction "2_2") (pintype "passive"))
      (node (ref "QF1") (pin "3") (pinfunction "3_3") (pintype "passive"))
      (node (ref "U1") (pin "3") (pinfunction "PC14-OSC32-IN_3") (pintype "bidirectional"))
    )
    (net (code "27") (name "HFXOUT") (class "Default")
      (node (ref "C31") (pin "2") (pinfunction "2_2") (pintype "passive"))
      (node (ref "QF1") (pin "1") (pinfunction "1_1") (pintype "passive"))
      (node (ref "U1") (pin "4") (pinfunction "PC15-OSC32-OUT_4") (pintype "bidirectional"))
    )
    (net (code "28") (name "INT") (class "Default")
      (node (ref "IC3") (pin "B3") (pinfunction "~{INT}_B3") (pintype "bidirectional"))
      (node (ref "R4") (pin "1") (pinfunction "1_1") (pintype "passive"))
    )
    (net (code "29") (name "INT1") (class "Default")
      (node (ref "IC1") (pin "G4") (pinfunction "INT1_G4") (pintype "bidirectional"))
      (node (ref "U1") (pin "27") (pinfunction "PB1_27") (pintype "bidirectional"))
    )
    (net (code "30") (name "INT2") (class "Default")
      (node (ref "IC1") (pin "G5") (pinfunction "INT2_G5") (pintype "bidirectional"))
      (node (ref "U1") (pin "26") (pinfunction "PB0_26") (pintype "bidirectional"))
    )
    (net (code "31") (name "KEY") (class "Default")
      (node (ref "JP2") (pin "3") (pinfunction "3_3") (pintype "passive"))
      (node (ref "JP6") (pin "1") (pinfunction "1_1") (pintype "passive"))
    )
    (net (code "32") (name "LA") (class "Default")
      (node (ref "IC1") (pin "A7") (pinfunction "ECG_EL1_A7") (pintype "bidirectional"))
      (node (ref "JP1") (pin "2") (pinfunction "2_2") (pintype "passive"))
    )
    (net (code "33") (name "LAD") (class "Default")
      (node (ref "C28") (pin "1") (pinfunction "1_1") (pintype "passive"))
      (node (ref "C39") (pin "1") (pinfunction "1_1") (pintype "passive"))
      (node (ref "JP3") (pin "2") (pinfunction "2_2") (pintype "passive"))
      (node (ref "R21") (pin "2") (pinfunction "2_2") (pintype "passive"))
    )
    (net (code "34") (name "LBI") (class "Default")
      (node (ref "IC2") (pin "2") (pinfunction "LBI_2") (pintype "input"))
      (node (ref "RA") (pin "2") (pinfunction "2_2") (pintype "passive"))
      (node (ref "RB") (pin "1") (pinfunction "1_1") (pintype "passive"))
    )
    (net (code "35") (name "LBO") (class "Default")
      (node (ref "IC2") (pin "3") (pinfunction "LBO/_3") (pintype "output"))
      (node (ref "R14") (pin "2") (pinfunction "2_2") (pintype "passive"))
    )
    (net (code "36") (name "LED1_DRV") (class "Default")
      (node (ref "IC1") (pin "G3") (pinfunction "LED1_DRV_G3") (pintype "bidirectional"))
      (node (ref "LED1") (pin "3") (pinfunction "CATHODE_EMITTER_1(530_NM)_3") (pintype "bidirectional"))
    )
    (net (code "37") (name "LED2_DRV") (class "Default")
      (node (ref "IC1") (pin "F3") (pinfunction "LED2_DRV_F3") (pintype "bidirectional"))
      (node (ref "LED1") (pin "1") (pinfunction "CATHODE_EMITTER_3_(940_NM)_1") (pintype "bidirectional"))
    )
    (net (code "38") (name "LED3_DRV") (class "Default")
      (node (ref "IC1") (pin "G2") (pinfunction "LED3_DRV_G2") (pintype "bidirectional"))
      (node (ref "LED1") (pin "4") (pinfunction "CATHODE_EMITTER_2(655_NM)_4") (pintype "bidirectional"))
    )
    (net (code "39") (name "LEDP") (class "Default")
      (node (ref "IC3") (pin "D1") (pinfunction "LED_D1") (pintype "bidirectional"))
      (node (ref "LED2") (pin "C") (pinfunction "C_C") (pintype "passive"))
    )
    (net (code "40") (name "LX") (class "Default")
      (node (ref "D3") (pin "1") (pinfunction "A_1") (pintype "passive"))
      (node (ref "IC2") (pin "9") (pinfunction "LX_9") (pintype "passive"))
    )
    (net (code "41") (name "MISO") (class "Default")
      (node (ref "IC1") (pin "F4") (pinfunction "SDO/ADDR_F4") (pintype "bidirectional"))
      (node (ref "JP5") (pin "2") (pinfunction "2_2") (pintype "passive"))
      (node (ref "U$1") (pin "SO/SIO1") (pinfunction "SSO/SIO1_SO/SIO1") (pintype "bidirectional"))
      (node (ref "U1") (pin "22") (pinfunction "PA6_22") (pintype "bidirectional"))
    )
    (net (code "42") (name "MON") (class "Default")
      (node (ref "IC3") (pin "B4") (pinfunction "MON_B4") (pintype "bidirectional"))
      (node (ref "JP2") (pin "1") (pinfunction "1_1") (pintype "passive"))
    )
    (net (code "43") (name "MOSI") (class "Default")
      (node (ref "IC1") (pin "E5") (pinfunction "SDI/SDA_E5") (pintype "bidirectional"))
      (node (ref "JP5") (pin "3") (pinfunction "3_3") (pintype "passive"))
      (node (ref "U$1") (pin "SI/SIO0") (pinfunction "SI/SIO0_SI/SIO0") (pintype "bidirectional"))
      (node (ref "U1") (pin "23") (pinfunction "PA7_23") (pintype "bidirectional"))
    )
    (net (code "44") (name "MPC0") (class "Default")
      (node (ref "IC3") (pin "E2") (pinfunction "MPC0_E2") (pintype "bidirectional"))
      (node (ref "JP7") (pin "1") (pinfunction "1_1") (pintype "passive"))
    )
    (net (code "45") (name "MPC1") (class "Default")
      (node (ref "IC3") (pin "E3") (pinfunction "MPC1_E3") (pintype "bidirectional"))
      (node (ref "R10") (pin "2") (pinfunction "2_2") (pintype "passive"))
    )
    (net (code "46") (name "Net-(C17-Pad1)") (class "Default")
      (node (ref "C17") (pin "1") (pinfunction "1_1") (pintype "passive"))
      (node (ref "R16") (pin "1") (pinfunction "1_1") (pintype "passive"))
      (node (ref "R18") (pin "1") (pinfunction "1_1") (pintype "passive"))
      (node (ref "R19") (pin "1") (pinfunction "1_1") (pintype "passive"))
      (node (ref "R20") (pin "2") (pinfunction "2_2") (pintype "passive"))
    )
    (net (code "47") (name "Net-(C28-Pad2)") (class "Default")
      (node (ref "C28") (pin "2") (pinfunction "2_2") (pintype "passive"))
      (node (ref "C38") (pin "1") (pinfunction "1_1") (pintype "passive"))
    )
    (net (code "48") (name "Net-(J1-Pad2)") (class "Default")
      (node (ref "J1") (pin "2") (pinfunction "2_2") (pintype "passive"))
      (node (ref "R23") (pin "1") (pinfunction "1_1") (pintype "passive"))
    )
    (net (code "49") (name "Net-(LED2-PadA)") (class "Default")
      (node (ref "LED2") (pin "A") (pinfunction "A_A") (pintype "passive"))
      (node (ref "R7") (pin "1") (pinfunction "1_1") (pintype "passive"))
    )
    (net (code "50") (name "Net-(LED3-PadA)") (class "Default")
      (node (ref "LED3") (pin "A") (pinfunction "A_A") (pintype "passive"))
      (node (ref "R9") (pin "1") (pinfunction "1_1") (pintype "passive"))
    )
    (net (code "51") (name "Net-(R11-Pad1)") (class "Default")
      (node (ref "R11") (pin "1") (pinfunction "1_1") (pintype "passive"))
      (node (ref "R12") (pin "1") (pinfunction "1_1") (pintype "passive"))
      (node (ref "R13") (pin "1") (pinfunction "1_1") (pintype "passive"))
      (node (ref "R8") (pin "1") (pinfunction "1_1") (pintype "passive"))
    )
    (net (code "52") (name "Net-(R16-Pad2)") (class "Default")
      (node (ref "R16") (pin "2") (pinfunction "2_2") (pintype "passive"))
      (node (ref "U$4") (pin "1") (pinfunction "1_1") (pintype "passive"))
    )
    (net (code "53") (name "Net-(R21-Pad1)") (class "Default")
      (node (ref "R21") (pin "1") (pinfunction "1_1") (pintype "passive"))
      (node (ref "U$3") (pin "2") (pinfunction "2_2") (pintype "passive"))
    )
    (net (code "54") (name "Net-(R22-Pad1)") (class "Default")
      (node (ref "R22") (pin "1") (pinfunction "1_1") (pintype "passive"))
      (node (ref "U$5") (pin "2") (pinfunction "2_2") (pintype "passive"))
    )
    (net (code "55") (name "Net-(U1-BOOT0)") (class "Default")
      (node (ref "R23") (pin "2") (pinfunction "2_2") (pintype "passive"))
      (node (ref "U1") (pin "60") (pinfunction "BOOT0_60") (pintype "input"))
    )
    (net (code "56") (name "PD1_IN") (class "Default")
      (node (ref "D5") (pin "1") (pinfunction "PD_PIN_1_CATHODE_1") (pintype "bidirectional"))
      (node (ref "D5") (pin "2") (pinfunction "PD_PIN_2_CATHODE_2") (pintype "bidirectional"))
      (node (ref "D5") (pin "3") (pinfunction "PD_PIN_3_CATHODE_3") (pintype "bidirectional"))
      (node (ref "D5") (pin "4") (pinfunction "PD_PIN_4_CATHODE_4") (pintype "bidirectional"))
      (node (ref "D5") (pin "6") (pinfunction "PD_PIN_6_CATHODE_6") (pintype "bidirectional"))
      (node (ref "D5") (pin "7") (pinfunction "PD_PIN_7_CATHODE_7") (pintype "bidirectional"))
      (node (ref "D5") (pin "8") (pinfunction "PD_PIN_8_CATHODE_8") (pintype "bidirectional"))
      (node (ref "IC1") (pin "C1") (pinfunction "PD1_IN_C1") (pintype "bidirectional"))
    )
    (net (code "57") (name "PD2_IN") (class "Default")
      (node (ref "D1") (pin "1") (pinfunction "PD_PIN_1_CATHODE_1") (pintype "bidirectional"))
      (node (ref "D1") (pin "2") (pinfunction "PD_PIN_2_CATHODE_2") (pintype "bidirectional"))
      (node (ref "D1") (pin "3") (pinfunction "PD_PIN_3_CATHODE_3") (pintype "bidirectional"))
      (node (ref "D1") (pin "4") (pinfunction "PD_PIN_4_CATHODE_4") (pintype "bidirectional"))
      (node (ref "D1") (pin "6") (pinfunction "PD_PIN_6_CATHODE_6") (pintype "bidirectional"))
      (node (ref "D1") (pin "7") (pinfunction "PD_PIN_7_CATHODE_7") (pintype "bidirectional"))
      (node (ref "D1") (pin "8") (pinfunction "PD_PIN_8_CATHODE_8") (pintype "bidirectional"))
      (node (ref "IC1") (pin "D1") (pinfunction "PD2_IN_D1") (pintype "bidirectional"))
    )
    (net (code "58") (name "PD3_IN") (class "Default")
      (node (ref "D6") (pin "1") (pinfunction "PD_PIN_1_CATHODE_1") (pintype "bidirectional"))
      (node (ref "D6") (pin "2") (pinfunction "PD_PIN_2_CATHODE_2") (pintype "bidirectional"))
      (node (ref "D6") (pin "3") (pinfunction "PD_PIN_3_CATHODE_3") (pintype "bidirectional"))
      (node (ref "D6") (pin "4") (pinfunction "PD_PIN_4_CATHODE_4") (pintype "bidirectional"))
      (node (ref "D6") (pin "6") (pinfunction "PD_PIN_6_CATHODE_6") (pintype "bidirectional"))
      (node (ref "D6") (pin "7") (pinfunction "PD_PIN_7_CATHODE_7") (pintype "bidirectional"))
      (node (ref "D6") (pin "8") (pinfunction "PD_PIN_8_CATHODE_8") (pintype "bidirectional"))
      (node (ref "IC1") (pin "D2") (pinfunction "PD3_IN_D2") (pintype "bidirectional"))
    )
    (net (code "59") (name "PFN1") (class "Default")
      (node (ref "IC3") (pin "E4") (pinfunction "PFN1_E4") (pintype "bidirectional"))
      (node (ref "SW2") (pin "B") (pinfunction "S_B") (pintype "passive"))
      (node (ref "SW2") (pin "B'") (pinfunction "S1_B'") (pintype "passive"))
    )
    (net (code "60") (name "PFN2") (class "Default")
      (node (ref "IC3") (pin "D2") (pinfunction "PFN2_D2") (pintype "bidirectional"))
      (node (ref "JP7") (pin "2") (pinfunction "2_2") (pintype "passive"))
    )
    (net (code "61") (name "PGND") (class "Default")
      (node (ref "IC1") (pin "E1") (pinfunction "PGND_E1") (pintype "bidirectional"))
      (node (ref "R8") (pin "2") (pinfunction "2_2") (pintype "passive"))
    )
    (net (code "62") (name "RA") (class "Default")
      (node (ref "IC1") (pin "A6") (pinfunction "ECG_EL2_A6") (pintype "bidirectional"))
      (node (ref "JP1") (pin "1") (pinfunction "1_1") (pintype "passive"))
    )
    (net (code "63") (name "RAD") (class "Default")
      (node (ref "C38") (pin "2") (pinfunction "2_2") (pintype "passive"))
      (node (ref "C39") (pin "2") (pinfunction "2_2") (pintype "passive"))
      (node (ref "JP3") (pin "3") (pinfunction "3_3") (pintype "passive"))
      (node (ref "R22") (pin "2") (pinfunction "2_2") (pintype "passive"))
    )
    (net (code "64") (name "REF1676") (class "Default")
      (node (ref "C37") (pin "1") (pinfunction "1_1") (pintype "passive"))
      (node (ref "IC2") (pin "5") (pinfunction "REF_5") (pintype "passive"))
    )
    (net (code "65") (name "RLD") (class "Default")
      (node (ref "IC1") (pin "C6") (pinfunction "ECG_EL3_C6") (pintype "bidirectional"))
      (node (ref "JP1") (pin "3") (pinfunction "3_3") (pintype "passive"))
    )
    (net (code "66") (name "RLDD") (class "Default")
      (node (ref "D4") (pin "2") (pinfunction "2_2") (pintype "passive"))
      (node (ref "JP3") (pin "1") (pinfunction "1_1") (pintype "passive"))
      (node (ref "U$4") (pin "2") (pinfunction "2_2") (pintype "passive"))
    )
    (net (code "67") (name "RST") (class "Default")
      (node (ref "C22") (pin "1") (pinfunction "1_1") (pintype "passive"))
      (node (ref "IC3") (pin "E1") (pinfunction "~{RST}_E1") (pintype "bidirectional"))
      (node (ref "R5") (pin "1") (pinfunction "1_1") (pintype "passive"))
      (node (ref "SW1") (pin "A") (pinfunction "P_A") (pintype "passive"))
      (node (ref "SW1") (pin "A'") (pinfunction "P1_A'") (pintype "passive"))
      (node (ref "U1") (pin "7") (pinfunction "NRST_7") (pintype "bidirectional"))
    )
    (net (code "68") (name "RTS1") (class "Default")
      (node (ref "JP10/FTDI") (pin "6") (pinfunction "6_6") (pintype "passive"))
      (node (ref "U1") (pin "61") (pinfunction "PB8_61") (pintype "bidirectional"))
    )
    (net (code "69") (name "RX0") (class "Default")
      (node (ref "IC6") (pin "4") (pinfunction "1Y_4") (pintype "bidirectional"))
      (node (ref "U1") (pin "17") (pinfunction "PA3_17") (pintype "bidirectional"))
    )
    (net (code "70") (name "RX1") (class "Default")
      (node (ref "JP4") (pin "4") (pinfunction "4_4") (pintype "passive"))
      (node (ref "U1") (pin "25") (pinfunction "PC5_25") (pintype "bidirectional"))
    )
    (net (code "71") (name "RXBLE") (class "Default")
      (node (ref "IC6") (pin "2") (pinfunction "1I0_2") (pintype "bidirectional"))
      (node (ref "JP6") (pin "5") (pinfunction "5_5") (pintype "passive"))
    )
    (net (code "72") (name "RXFTDI") (class "Default")
      (node (ref "IC6") (pin "3") (pinfunction "1I1_3") (pintype "bidirectional"))
      (node (ref "JP10/FTDI") (pin "5") (pinfunction "5_5") (pintype "passive"))
    )
    (net (code "73") (name "SCL") (class "Default")
      (node (ref "IC3") (pin "F1") (pinfunction "SDA_F1") (pintype "bidirectional"))
      (node (ref "IC4") (pin "4") (pinfunction "SCL_4") (pintype "bidirectional"))
      (node (ref "R2") (pin "1") (pinfunction "1_1") (pintype "passive"))
      (node (ref "U1") (pin "50") (pinfunction "PA15_50") (pintype "bidirectional"))
    )
    (net (code "74") (name "SCLK") (class "Default")
      (node (ref "IC1") (pin "E4") (pinfunction "SCLK/SCL_E4") (pintype "bidirectional"))
      (node (ref "JP5") (pin "4") (pinfunction "4_4") (pintype "passive"))
      (node (ref "U$1") (pin "SCLK") (pinfunction "SCLK_SCLK") (pintype "bidirectional"))
      (node (ref "U1") (pin "21") (pinfunction "PA5_21") (pintype "bidirectional"))
    )
    (net (code "75") (name "SDA") (class "Default")
      (node (ref "IC3") (pin "F2") (pinfunction "SCL_F2") (pintype "bidirectional"))
      (node (ref "IC4") (pin "1") (pinfunction "SDA_1") (pintype "bidirectional"))
      (node (ref "R3") (pin "1") (pinfunction "1_1") (pintype "passive"))
      (node (ref "U1") (pin "49") (pinfunction "PA14_49") (pintype "bidirectional"))
    )
    (net (code "76") (name "SETP") (class "Default")
      (node (ref "IC3") (pin "C5") (pinfunction "SET_C5") (pintype "bidirectional"))
      (node (ref "R1") (pin "2") (pinfunction "2_2") (pintype "passive"))
    )
    (net (code "77") (name "STATE") (class "Default")
      (node (ref "JP2") (pin "2") (pinfunction "2_2") (pintype "passive"))
      (node (ref "JP6") (pin "6") (pinfunction "6_6") (pintype "passive"))
    )
    (net (code "78") (name "SYS") (class "Default")
      (node (ref "C19") (pin "1") (pinfunction "1_1") (pintype "passive"))
      (node (ref "C20") (pin "1") (pinfunction "1_1") (pintype "passive"))
      (node (ref "IC3") (pin "C6") (pinfunction "SYS_1_C6") (pintype "bidirectional"))
      (node (ref "IC3") (pin "D6") (pinfunction "SYS_2_D6") (pintype "bidirectional"))
      (node (ref "Q1") (pin "3") (pinfunction "S_3") (pintype "passive"))
    )
    (net (code "79") (name "THM") (class "Default")
      (node (ref "IC3") (pin "F3") (pinfunction "THM_F3") (pintype "bidirectional"))
      (node (ref "R6") (pin "2") (pinfunction "2_2") (pintype "passive"))
      (node (ref "RT1") (pin "1") (pinfunction "1_1") (pintype "passive"))
    )
    (net (code "80") (name "TRIG") (class "Default")
      (node (ref "IC1") (pin "G6") (pinfunction "TRIG_G6") (pintype "bidirectional"))
      (node (ref "U1") (pin "55") (pinfunction "PB3_55") (pintype "bidirectional"))
    )
    (net (code "81") (name "TX0") (class "Default")
      (node (ref "IC6") (pin "7") (pinfunction "2Y_7") (pintype "bidirectional"))
      (node (ref "U1") (pin "16") (pinfunction "PA2_16") (pintype "bidirectional"))
    )
    (net (code "82") (name "TX1") (class "Default")
      (node (ref "JP4") (pin "3") (pinfunction "3_3") (pintype "passive"))
      (node (ref "U1") (pin "24") (pinfunction "PC4_24") (pintype "bidirectional"))
    )
    (net (code "83") (name "TXBLE") (class "Default")
      (node (ref "IC6") (pin "5") (pinfunction "2I0_5") (pintype "bidirectional"))
      (node (ref "JP6") (pin "4") (pinfunction "4_4") (pintype "passive"))
    )
    (net (code "84") (name "TXFTDI") (class "Default")
      (node (ref "IC6") (pin "6") (pinfunction "2I1_6") (pintype "bidirectional"))
      (node (ref "JP10/FTDI") (pin "4") (pinfunction "4_4") (pintype "passive"))
    )
    (net (code "85") (name "VMID_ECG") (class "Default")
      (node (ref "C1") (pin "2") (pinfunction "2_2") (pintype "passive"))
      (node (ref "IC1") (pin "E6") (pinfunction "VMID_ECG_E6") (pintype "bidirectional"))
    )
    (net (code "86") (name "VREF_ECG") (class "Default")
      (node (ref "C3") (pin "2") (pinfunction "2_2") (pintype "passive"))
      (node (ref "IC1") (pin "F6") (pinfunction "VREF_ECG_F6") (pintype "bidirectional"))
    )
    (net (code "87") (name "VREF_PPG") (class "Default")
      (node (ref "C2") (pin "2") (pinfunction "2_2") (pintype "passive"))
      (node (ref "IC1") (pin "E2") (pinfunction "VREF_PPG_E2") (pintype "bidirectional"))
    )
    (net (code "88") (name "VSIS") (class "Default")
      (node (ref "IC3") (pin "A2") (pinfunction "L1IN_A2") (pintype "bidirectional"))
      (node (ref "IC3") (pin "B2") (pinfunction "L2IN_B2") (pintype "bidirectional"))
      (node (ref "IC3") (pin "C2") (pinfunction "L3IN_C2") (pintype "bidirectional"))
    )
    (net (code "89") (name "WP") (class "Default")
      (node (ref "U$1") (pin "WP_N/SIO2") (pinfunction "WP_N/SIO2_WP_N/SIO2") (pintype "bidirectional"))
      (node (ref "U1") (pin "56") (pinfunction "PB4_56") (pintype "bidirectional"))
    )
    (net (code "90") (name "unconnected-(IC1-BIOZ_EL1-PadA3)") (class "Default")
      (node (ref "IC1") (pin "A3") (pinfunction "BIOZ_EL1_A3") (pintype "bidirectional"))
    )
    (net (code "91") (name "unconnected-(IC1-BIOZ_EL2A-PadA1)") (class "Default")
      (node (ref "IC1") (pin "A1") (pinfunction "BIOZ_EL2A_A1") (pintype "bidirectional"))
    )
    (net (code "92") (name "unconnected-(IC1-BIOZ_EL2B-PadB1)") (class "Default")
      (node (ref "IC1") (pin "B1") (pinfunction "BIOZ_EL2B_B1") (pintype "bidirectional"))
    )
    (net (code "93") (name "unconnected-(IC1-BIOZ_EL3A-PadA2)") (class "Default")
      (node (ref "IC1") (pin "A2") (pinfunction "BIOZ_EL3A_A2") (pintype "bidirectional"))
    )
    (net (code "94") (name "unconnected-(IC1-BIOZ_EL3B-PadB2)") (class "Default")
      (node (ref "IC1") (pin "B2") (pinfunction "BIOZ_EL3B_B2") (pintype "bidirectional"))
    )
    (net (code "95") (name "unconnected-(IC1-BIOZ_EL4-PadA4)") (class "Default")
      (node (ref "IC1") (pin "A4") (pinfunction "BIOZ_EL4_A4") (pintype "bidirectional"))
    )
    (net (code "96") (name "unconnected-(IC1-CAL1-PadA5)") (class "Default")
      (node (ref "IC1") (pin "A5") (pinfunction "CAL1_A5") (pintype "bidirectional"))
    )
    (net (code "97") (name "unconnected-(IC1-CAL2-PadB5)") (class "Default")
      (node (ref "IC1") (pin "B5") (pinfunction "CAL2_B5") (pintype "bidirectional"))
    )
    (net (code "98") (name "unconnected-(IC1-CAL3-PadB4)") (class "Default")
      (node (ref "IC1") (pin "B4") (pinfunction "CAL3_B4") (pintype "bidirectional"))
    )
    (net (code "99") (name "unconnected-(IC1-CAL4-PadB3)") (class "Default")
      (node (ref "IC1") (pin "B3") (pinfunction "CAL4_B3") (pintype "bidirectional"))
    )
    (net (code "100") (name "unconnected-(IC1-DRVSJ-PadC5)") (class "Default")
      (node (ref "IC1") (pin "C5") (pinfunction "DRVSJ_C5") (pintype "bidirectional"))
    )
    (net (code "101") (name "unconnected-(IC1-DRVXC-PadD5)") (class "Default")
      (node (ref "IC1") (pin "D5") (pinfunction "DRVXC_D5") (pintype "bidirectional"))
    )
    (net (code "102") (name "unconnected-(IC1-DRVXR-PadC4)") (class "Default")
      (node (ref "IC1") (pin "C4") (pinfunction "DRVXR_C4") (pintype "bidirectional"))
    )
    (net (code "103") (name "unconnected-(IC1-FCLK-PadF5)") (class "Default")
      (node (ref "IC1") (pin "F5") (pinfunction "FCLK_F5") (pintype "bidirectional"))
    )
    (net (code "104") (name "unconnected-(IC1-LDO_OUT-PadE7)") (class "Default")
      (node (ref "IC1") (pin "E7") (pinfunction "LDO_OUT_E7") (pintype "bidirectional"))
    )
    (net (code "105") (name "unconnected-(IC1-LED4_DRV-PadF2)") (class "Default")
      (node (ref "IC1") (pin "F2") (pinfunction "LED4_DRV_F2") (pintype "bidirectional"))
    )
    (net (code "106") (name "unconnected-(IC1-LED5_DRV-PadG1)") (class "Default")
      (node (ref "IC1") (pin "G1") (pinfunction "LED5_DRV_G1") (pintype "bidirectional"))
    )
    (net (code "107") (name "unconnected-(IC1-LED6_DRV-PadF1)") (class "Default")
      (node (ref "IC1") (pin "F1") (pinfunction "LED6_DRV_F1") (pintype "bidirectional"))
    )
    (net (code "108") (name "unconnected-(IC1-PD4_IN-PadC2)") (class "Default")
      (node (ref "IC1") (pin "C2") (pinfunction "PD4_IN_C2") (pintype "bidirectional"))
    )
    (net (code "109") (name "unconnected-(IC1-RLD_INV-PadC7)") (class "Default")
      (node (ref "IC1") (pin "C7") (pinfunction "RLD_INV_C7") (pintype "bidirectional"))
    )
    (net (code "110") (name "unconnected-(IC3-B1LX-PadF6)") (class "Default")
      (node (ref "IC3") (pin "F6") (pinfunction "B1LX_F6") (pintype "bidirectional"))
    )
    (net (code "111") (name "unconnected-(IC3-B1OUT-PadF5)") (class "Default")
      (node (ref "IC3") (pin "F5") (pinfunction "B1OUT_F5") (pintype "bidirectional"))
    )
    (net (code "112") (name "unconnected-(IC3-B2LX-PadA6)") (class "Default")
      (node (ref "IC3") (pin "A6") (pinfunction "B2LX_A6") (pintype "bidirectional"))
    )
    (net (code "113") (name "unconnected-(IC3-B2OUT-PadA5)") (class "Default")
      (node (ref "IC3") (pin "A5") (pinfunction "B2OUT_A5") (pintype "bidirectional"))
    )
    (net (code "114") (name "unconnected-(IC6-3I0-Pad11)") (class "Default")
      (node (ref "IC6") (pin "11") (pinfunction "3I0_11") (pintype "bidirectional"))
    )
    (net (code "115") (name "unconnected-(IC6-3I1-Pad10)") (class "Default")
      (node (ref "IC6") (pin "10") (pinfunction "3I1_10") (pintype "bidirectional"))
    )
    (net (code "116") (name "unconnected-(IC6-3Y-Pad9)") (class "Default")
      (node (ref "IC6") (pin "9") (pinfunction "3Y_9") (pintype "bidirectional"))
    )
    (net (code "117") (name "unconnected-(IC6-4I0-Pad14)") (class "Default")
      (node (ref "IC6") (pin "14") (pinfunction "4I0_14") (pintype "bidirectional"))
    )
    (net (code "118") (name "unconnected-(IC6-4I1-Pad13)") (class "Default")
      (node (ref "IC6") (pin "13") (pinfunction "4I1_13") (pintype "bidirectional"))
    )
    (net (code "119") (name "unconnected-(IC6-4Y-Pad12)") (class "Default")
      (node (ref "IC6") (pin "12") (pinfunction "4Y_12") (pintype "bidirectional"))
    )
    (net (code "120") (name "unconnected-(LED1-NC-Pad6)") (class "Default")
      (node (ref "LED1") (pin "6") (pinfunction "NC_6") (pintype "no_connect"))
    )
    (net (code "121") (name "unconnected-(U$2-Pad2)") (class "Default")
      (node (ref "U$2") (pin "2") (pinfunction "2_2") (pintype "input"))
    )
    (net (code "122") (name "unconnected-(U$2-Pad3)") (class "Default")
      (node (ref "U$2") (pin "3") (pinfunction "3_3") (pintype "input"))
    )
    (net (code "123") (name "unconnected-(U$2-Pad4)") (class "Default")
      (node (ref "U$2") (pin "4") (pinfunction "4_4") (pintype "input"))
    )
    (net (code "124") (name "unconnected-(U1-PA0-Pad14)") (class "Default")
      (node (ref "U1") (pin "14") (pinfunction "PA0_14") (pintype "bidirectional"))
    )
    (net (code "125") (name "unconnected-(U1-PA1-Pad15)") (class "Default")
      (node (ref "U1") (pin "15") (pinfunction "PA1_15") (pintype "bidirectional"))
    )
    (net (code "126") (name "unconnected-(U1-PA4-Pad20)") (class "Default")
      (node (ref "U1") (pin "20") (pinfunction "PA4_20") (pintype "bidirectional"))
    )
    (net (code "127") (name "unconnected-(U1-PA8-Pad41)") (class "Default")
      (node (ref "U1") (pin "41") (pinfunction "PA8_41") (pintype "bidirectional"))
    )
    (net (code "128") (name "unconnected-(U1-PA9-Pad42)") (class "Default")
      (node (ref "U1") (pin "42") (pinfunction "PA9_42") (pintype "bidirectional"))
    )
    (net (code "129") (name "unconnected-(U1-PA10-Pad43)") (class "Default")
      (node (ref "U1") (pin "43") (pinfunction "PA10_43") (pintype "bidirectional"))
    )
    (net (code "130") (name "unconnected-(U1-PA11-Pad44)") (class "Default")
      (node (ref "U1") (pin "44") (pinfunction "PA11_44") (pintype "bidirectional"))
    )
    (net (code "131") (name "unconnected-(U1-PA12-Pad45)") (class "Default")
      (node (ref "U1") (pin "45") (pinfunction "PA12_45") (pintype "bidirectional"))
    )
    (net (code "132") (name "unconnected-(U1-PA13-Pad46)") (class "Default")
      (node (ref "U1") (pin "46") (pinfunction "PA13_46") (pintype "bidirectional"))
    )
    (net (code "133") (name "unconnected-(U1-PB10-Pad29)") (class "Default")
      (node (ref "U1") (pin "29") (pinfunction "PB10_29") (pintype "bidirectional"))
    )
    (net (code "134") (name "unconnected-(U1-PB11-Pad30)") (class "Default")
      (node (ref "U1") (pin "30") (pinfunction "PB11_30") (pintype "bidirectional"))
    )
    (net (code "135") (name "unconnected-(U1-PB12-Pad33)") (class "Default")
      (node (ref "U1") (pin "33") (pinfunction "PB12_33") (pintype "bidirectional"))
    )
    (net (code "136") (name "unconnected-(U1-PB13-Pad34)") (class "Default")
      (node (ref "U1") (pin "34") (pinfunction "PB13_34") (pintype "bidirectional"))
    )
    (net (code "137") (name "unconnected-(U1-PB14-Pad35)") (class "Default")
      (node (ref "U1") (pin "35") (pinfunction "PB14_35") (pintype "bidirectional"))
    )
    (net (code "138") (name "unconnected-(U1-PB15-Pad36)") (class "Default")
      (node (ref "U1") (pin "36") (pinfunction "PB15_36") (pintype "bidirectional"))
    )
    (net (code "139") (name "unconnected-(U1-PC0-Pad8)") (class "Default")
      (node (ref "U1") (pin "8") (pinfunction "PC0_8") (pintype "bidirectional"))
    )
    (net (code "140") (name "unconnected-(U1-PC1-Pad9)") (class "Default")
      (node (ref "U1") (pin "9") (pinfunction "PC1_9") (pintype "bidirectional"))
    )
    (net (code "141") (name "unconnected-(U1-PC2-Pad10)") (class "Default")
      (node (ref "U1") (pin "10") (pinfunction "PC2_10") (pintype "bidirectional"))
    )
    (net (code "142") (name "unconnected-(U1-PC3-Pad11)") (class "Default")
      (node (ref "U1") (pin "11") (pinfunction "PC3_11") (pintype "bidirectional"))
    )
    (net (code "143") (name "unconnected-(U1-PC6-Pad37)") (class "Default")
      (node (ref "U1") (pin "37") (pinfunction "PC6_37") (pintype "bidirectional"))
    )
    (net (code "144") (name "unconnected-(U1-PC7-Pad38)") (class "Default")
      (node (ref "U1") (pin "38") (pinfunction "PC7_38") (pintype "bidirectional"))
    )
    (net (code "145") (name "unconnected-(U1-PC8-Pad39)") (class "Default")
      (node (ref "U1") (pin "39") (pinfunction "PC8_39") (pintype "bidirectional"))
    )
    (net (code "146") (name "unconnected-(U1-PC9-Pad40)") (class "Default")
      (node (ref "U1") (pin "40") (pinfunction "PC9_40") (pintype "bidirectional"))
    )
    (net (code "147") (name "unconnected-(U1-PC10-Pad51)") (class "Default")
      (node (ref "U1") (pin "51") (pinfunction "PC10_51") (pintype "bidirectional"))
    )
    (net (code "148") (name "unconnected-(U1-PC11-Pad52)") (class "Default")
      (node (ref "U1") (pin "52") (pinfunction "PC11_52") (pintype "bidirectional"))
    )
    (net (code "149") (name "unconnected-(U1-PC12-Pad53)") (class "Default")
      (node (ref "U1") (pin "53") (pinfunction "PC12_53") (pintype "bidirectional"))
    )
    (net (code "150") (name "unconnected-(U1-PC13-Pad2)") (class "Default")
      (node (ref "U1") (pin "2") (pinfunction "PC13_2") (pintype "bidirectional"))
    )
    (net (code "151") (name "unconnected-(U1-PD2-Pad54)") (class "Default")
      (node (ref "U1") (pin "54") (pinfunction "PD2_54") (pintype "bidirectional"))
    )
    (net (code "152") (name "unconnected-(U1-PF0-OSC-IN-Pad5)") (class "Default")
      (node (ref "U1") (pin "5") (pinfunction "PF0-OSC-IN_5") (pintype "bidirectional"))
    )
    (net (code "153") (name "unconnected-(U1-PF1-OSC-OUT-Pad6)") (class "Default")
      (node (ref "U1") (pin "6") (pinfunction "PF1-OSC-OUT_6") (pintype "bidirectional"))
    )
  )
)
